# openLRS-APM.net
KiCad netlist of a schematic drawn in EAGLE
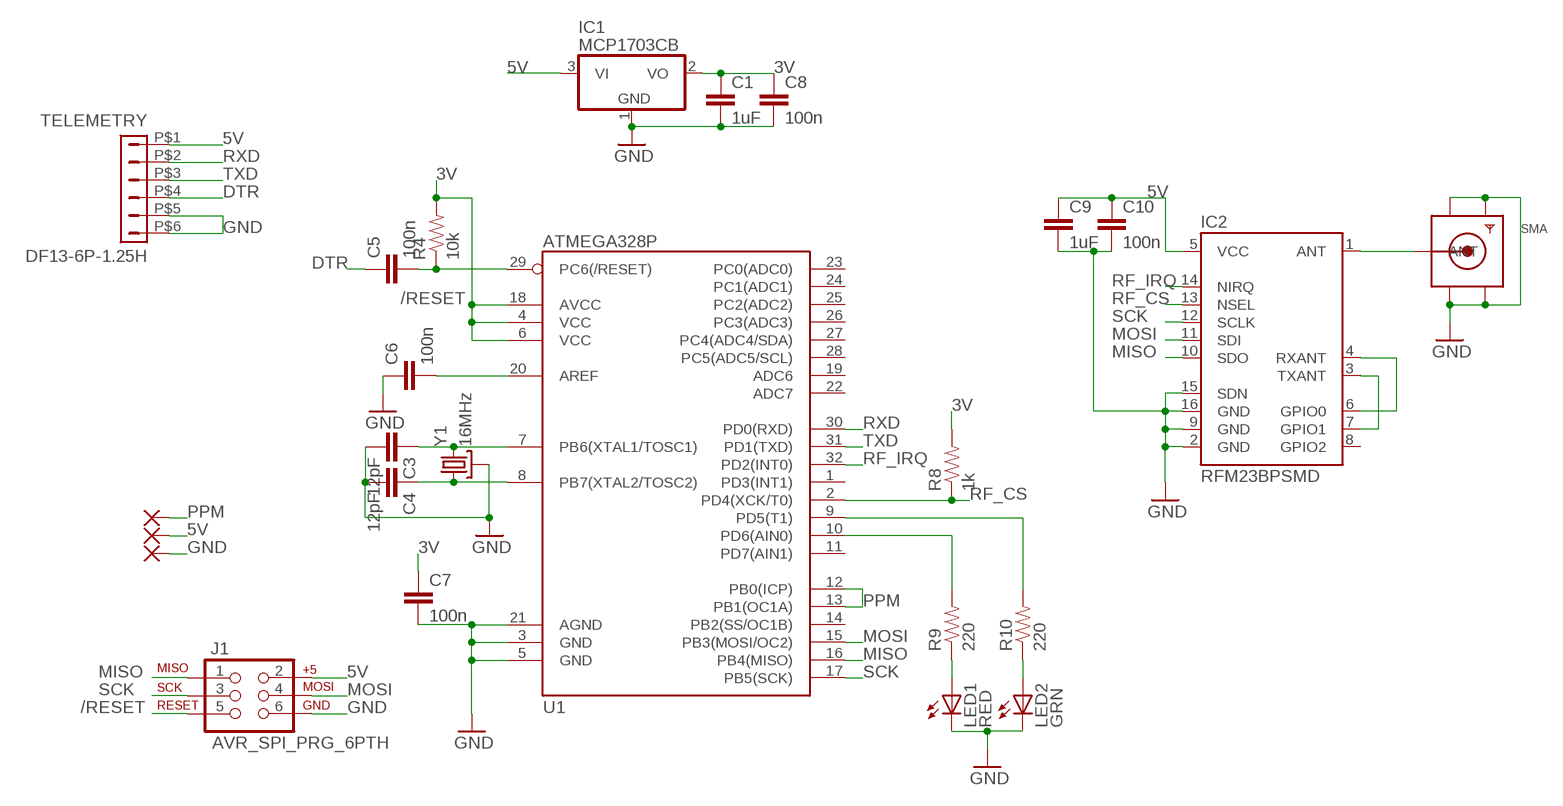
[diagram p0: schematic, sheet 1]

(export (version "E")
  (design (tool "Eeschema 10.0.6"))
  (components
    (comp (ref "C1")
      (value "1uF")
      (footprint "eagle-import:0805")
      (libsource (lib "eagle-import") (part "CAP0805"))
    )
    (comp (ref "C3")
      (value "12pF")
      (footprint "eagle-import:0805")
      (libsource (lib "eagle-import") (part "CAP0805"))
    )
    (comp (ref "C4")
      (value "12pF")
      (footprint "eagle-import:0805")
      (libsource (lib "eagle-import") (part "CAP0805"))
    )
    (comp (ref "C5")
      (value "100n")
      (footprint "eagle-import:0805")
      (libsource (lib "eagle-import") (part "CAP0805"))
    )
    (comp (ref "C6")
      (value "100n")
      (footprint "eagle-import:0805")
      (libsource (lib "eagle-import") (part "CAP0805"))
    )
    (comp (ref "C7")
      (value "100n")
      (footprint "eagle-import:0805")
      (libsource (lib "eagle-import") (part "CAP0805"))
    )
    (comp (ref "C8")
      (value "100n")
      (footprint "eagle-import:0805")
      (libsource (lib "eagle-import") (part "CAP0805"))
    )
    (comp (ref "C9")
      (value "1uF")
      (footprint "eagle-import:0805")
      (libsource (lib "eagle-import") (part "CAP0805"))
    )
    (comp (ref "C10")
      (value "100n")
      (footprint "eagle-import:0805")
      (libsource (lib "eagle-import") (part "CAP0805"))
    )
    (comp (ref "GND")
      (value "WIREPADSMD1,27-254")
      (footprint "eagle-import:SMD1,27-2,54")
      (libsource (lib "eagle-import") (part "WIREPADSMD1,27-254"))
    )
    (comp (ref "IC1")
      (value "MCP1703CB")
      (footprint "eagle-import:SOT23")
      (libsource (lib "eagle-import") (part "MCP1703CB"))
    )
    (comp (ref "IC2")
      (value "RFM23BPSMD")
      (footprint "eagle-import:RFM23BP-S2")
      (libsource (lib "eagle-import") (part "RFM23BPSMD"))
    )
    (comp (ref "J1")
      (value "AVR_SPI_PRG_6PTH")
      (footprint "eagle-import:2X3")
      (libsource (lib "eagle-import") (part "AVR_SPI_PRG_6PTH"))
    )
    (comp (ref "LED1")
      (value "RED")
      (footprint "eagle-import:SML0805")
      (libsource (lib "eagle-import") (part "LEDSML0805"))
    )
    (comp (ref "LED2")
      (value "GRN")
      (footprint "eagle-import:SML0805")
      (libsource (lib "eagle-import") (part "LEDSML0805"))
    )
    (comp (ref "PPM")
      (value "WIREPADSMD1,27-254")
      (footprint "eagle-import:SMD1,27-2,54")
      (libsource (lib "eagle-import") (part "WIREPADSMD1,27-254"))
    )
    (comp (ref "R4")
      (value "10k")
      (footprint "eagle-import:0805")
      (libsource (lib "eagle-import") (part "RESISTOR0805-RES"))
    )
    (comp (ref "R8")
      (value "1k")
      (footprint "eagle-import:0805")
      (libsource (lib "eagle-import") (part "RESISTOR0805-RES"))
    )
    (comp (ref "R9")
      (value "220")
      (footprint "eagle-import:0805")
      (libsource (lib "eagle-import") (part "RESISTOR0805-RES"))
    )
    (comp (ref "R10")
      (value "220")
      (footprint "eagle-import:0805")
      (libsource (lib "eagle-import") (part "RESISTOR0805-RES"))
    )
    (comp (ref "SMA")
      (value "SMACONNECTOR_EDGE")
      (footprint "eagle-import:SMA_EDGELAUNCH")
      (libsource (lib "eagle-import") (part "SMACONNECTOR_EDGE"))
    )
    (comp (ref "TELEMETRY")
      (value "DF13-6P-1.25H")
      (footprint "eagle-import:DF13A-6P-1.25H")
      (libsource (lib "eagle-import") (part "DF13-6P-1.25H"))
    )
    (comp (ref "U1")
      (value "ATMEGA328P")
      (footprint "eagle-import:TQFP32-08")
      (libsource (lib "eagle-import") (part "ATMEGA328_SMT"))
    )
    (comp (ref "VCC")
      (value "WIREPADSMD1,27-254")
      (footprint "eagle-import:SMD1,27-2,54")
      (libsource (lib "eagle-import") (part "WIREPADSMD1,27-254"))
    )
    (comp (ref "Y1")
      (value "16MHz")
      (footprint "eagle-import:CRYSTAL-SMD-5X3")
      (libsource (lib "eagle-import") (part "CRYSTAL3.2X2.5"))
    )
  )
  (nets
    (net (code "1") (name "/3V") (class "Default")
      (node (ref "C1") (pin "1") (pinfunction "1_1") (pintype "passive"))
      (node (ref "C7") (pin "1") (pinfunction "1_1") (pintype "passive"))
      (node (ref "C8") (pin "1") (pinfunction "1_1") (pintype "passive"))
      (node (ref "IC1") (pin "2") (pinfunction "VO_2") (pintype "passive"))
      (node (ref "R4") (pin "2") (pinfunction "2_2") (pintype "passive"))
      (node (ref "R8") (pin "2") (pinfunction "2_2") (pintype "passive"))
      (node (ref "U1") (pin "18") (pinfunction "AVCC_18") (pintype "bidirectional"))
      (node (ref "U1") (pin "4") (pinfunction "VCC_4") (pintype "bidirectional"))
      (node (ref "U1") (pin "6") (pinfunction "VCC_6") (pintype "bidirectional"))
    )
    (net (code "2") (name "/5V") (class "Default")
      (node (ref "C10") (pin "1") (pinfunction "1_1") (pintype "passive"))
      (node (ref "C9") (pin "1") (pinfunction "1_1") (pintype "passive"))
      (node (ref "IC1") (pin "3") (pinfunction "VI_3") (pintype "input"))
      (node (ref "IC2") (pin "5") (pinfunction "VCC_5") (pintype "bidirectional"))
      (node (ref "J1") (pin "2") (pinfunction "2_2") (pintype "passive"))
      (node (ref "TELEMETRY") (pin "P$1") (pinfunction "1_P$1") (pintype "passive"))
      (node (ref "VCC") (pin "1") (pinfunction "P_1") (pintype "passive"))
    )
    (net (code "3") (name "/DTR") (class "Default")
      (node (ref "C5") (pin "1") (pinfunction "1_1") (pintype "passive"))
      (node (ref "TELEMETRY") (pin "P$4") (pinfunction "4_P$4") (pintype "passive"))
    )
    (net (code "4") (name "/MISO") (class "Default")
      (node (ref "IC2") (pin "10") (pinfunction "SDO_10") (pintype "output"))
      (node (ref "J1") (pin "1") (pinfunction "1_1") (pintype "passive"))
      (node (ref "U1") (pin "16") (pinfunction "PB4(MISO)_16") (pintype "bidirectional"))
    )
    (net (code "5") (name "/MOSI") (class "Default")
      (node (ref "IC2") (pin "11") (pinfunction "SDI_11") (pintype "input"))
      (node (ref "J1") (pin "4") (pinfunction "4_4") (pintype "passive"))
      (node (ref "U1") (pin "15") (pinfunction "PB3(MOSI/OC2)_15") (pintype "bidirectional"))
    )
    (net (code "6") (name "/PPM") (class "Default")
      (node (ref "PPM") (pin "1") (pinfunction "P_1") (pintype "passive"))
      (node (ref "U1") (pin "12") (pinfunction "PB0(ICP)_12") (pintype "bidirectional"))
      (node (ref "U1") (pin "13") (pinfunction "PB1(OC1A)_13") (pintype "bidirectional"))
    )
    (net (code "7") (name "/RF_CS") (class "Default")
      (node (ref "IC2") (pin "13") (pinfunction "NSEL_13") (pintype "input"))
      (node (ref "R8") (pin "1") (pinfunction "1_1") (pintype "passive"))
      (node (ref "U1") (pin "2") (pinfunction "PD4(XCK/T0)_2") (pintype "bidirectional"))
    )
    (net (code "8") (name "/RF_IRQ") (class "Default")
      (node (ref "IC2") (pin "14") (pinfunction "NIRQ_14") (pintype "output"))
      (node (ref "U1") (pin "32") (pinfunction "PD2(INT0)_32") (pintype "bidirectional"))
    )
    (net (code "9") (name "/RXD") (class "Default")
      (node (ref "TELEMETRY") (pin "P$2") (pinfunction "2_P$2") (pintype "passive"))
      (node (ref "U1") (pin "30") (pinfunction "PD0(RXD)_30") (pintype "bidirectional"))
    )
    (net (code "10") (name "/SCK") (class "Default")
      (node (ref "IC2") (pin "12") (pinfunction "SCLK_12") (pintype "input"))
      (node (ref "J1") (pin "3") (pinfunction "3_3") (pintype "passive"))
      (node (ref "U1") (pin "17") (pinfunction "PB5(SCK)_17") (pintype "bidirectional"))
    )
    (net (code "11") (name "/TXD") (class "Default")
      (node (ref "TELEMETRY") (pin "P$3") (pinfunction "3_P$3") (pintype "passive"))
      (node (ref "U1") (pin "31") (pinfunction "PD1(TXD)_31") (pintype "bidirectional"))
    )
    (net (code "12") (name "/{slash}RESET") (class "Default")
      (node (ref "C5") (pin "2") (pinfunction "2_2") (pintype "passive"))
      (node (ref "J1") (pin "5") (pinfunction "5_5") (pintype "passive"))
      (node (ref "R4") (pin "1") (pinfunction "1_1") (pintype "passive"))
      (node (ref "U1") (pin "29") (pinfunction "PC6(/RESET)_29") (pintype "bidirectional"))
    )
    (net (code "13") (name "GND") (class "Default")
      (node (ref "C1") (pin "2") (pinfunction "2_2") (pintype "passive"))
      (node (ref "C10") (pin "2") (pinfunction "2_2") (pintype "passive"))
      (node (ref "C3") (pin "2") (pinfunction "2_2") (pintype "passive"))
      (node (ref "C4") (pin "2") (pinfunction "2_2") (pintype "passive"))
      (node (ref "C6") (pin "1") (pinfunction "1_1") (pintype "passive"))
      (node (ref "C7") (pin "2") (pinfunction "2_2") (pintype "passive"))
      (node (ref "C8") (pin "2") (pinfunction "2_2") (pintype "passive"))
      (node (ref "C9") (pin "2") (pinfunction "2_2") (pintype "passive"))
      (node (ref "GND") (pin "1") (pinfunction "P_1") (pintype "passive"))
      (node (ref "IC1") (pin "1") (pinfunction "GND_1") (pintype "passive"))
      (node (ref "IC2") (pin "15") (pinfunction "SDN_15") (pintype "input"))
      (node (ref "IC2") (pin "16") (pinfunction "GND_16") (pintype "power_in"))
      (node (ref "IC2") (pin "2") (pinfunction "GND_2") (pintype "power_in"))
      (node (ref "IC2") (pin "9") (pinfunction "GND_9") (pintype "power_in"))
      (node (ref "J1") (pin "6") (pinfunction "6_6") (pintype "passive"))
      (node (ref "LED1") (pin "C") (pinfunction "C_C") (pintype "passive"))
      (node (ref "LED2") (pin "C") (pinfunction "C_C") (pintype "passive"))
      (node (ref "SMA") (pin "GND@1") (pinfunction "GND4_GND@1") (pintype "power_in"))
      (node (ref "SMA") (pin "GND@2") (pinfunction "GND3_GND@2") (pintype "power_in"))
      (node (ref "SMA") (pin "GND@3") (pinfunction "GND2_GND@3") (pintype "power_in"))
      (node (ref "SMA") (pin "GND@4") (pinfunction "GND1_GND@4") (pintype "power_in"))
      (node (ref "TELEMETRY") (pin "P$5") (pinfunction "5_P$5") (pintype "passive"))
      (node (ref "TELEMETRY") (pin "P$6") (pinfunction "6_P$6") (pintype "passive"))
      (node (ref "U1") (pin "21") (pinfunction "AGND_21") (pintype "bidirectional"))
      (node (ref "U1") (pin "3") (pinfunction "GND_3") (pintype "bidirectional"))
      (node (ref "U1") (pin "5") (pinfunction "GND_5") (pintype "bidirectional"))
      (node (ref "Y1") (pin "2") (pinfunction "GND_2") (pintype "power_in"))
      (node (ref "Y1") (pin "4") (pinfunction "GND_4") (pintype "power_in"))
    )
    (net (code "14") (name "Net-(IC2-ANT)") (class "Default")
      (node (ref "IC2") (pin "1") (pinfunction "ANT_1") (pintype "bidirectional"))
      (node (ref "SMA") (pin "P") (pinfunction "ANT_P") (pintype "bidirectional"))
    )
    (net (code "15") (name "Net-(IC2-GPIO0)") (class "Default")
      (node (ref "IC2") (pin "4") (pinfunction "RXANT_4") (pintype "input"))
      (node (ref "IC2") (pin "6") (pinfunction "GPIO0_6") (pintype "bidirectional"))
    )
    (net (code "16") (name "Net-(IC2-GPIO1)") (class "Default")
      (node (ref "IC2") (pin "3") (pinfunction "TXANT_3") (pintype "input"))
      (node (ref "IC2") (pin "7") (pinfunction "GPIO1_7") (pintype "bidirectional"))
    )
    (net (code "17") (name "Net-(LED1-PadA)") (class "Default")
      (node (ref "LED1") (pin "A") (pinfunction "A_A") (pintype "passive"))
      (node (ref "R9") (pin "1") (pinfunction "1_1") (pintype "passive"))
    )
    (net (code "18") (name "Net-(LED2-PadA)") (class "Default")
      (node (ref "LED2") (pin "A") (pinfunction "A_A") (pintype "passive"))
      (node (ref "R10") (pin "1") (pinfunction "1_1") (pintype "passive"))
    )
    (net (code "19") (name "Net-(U1-AREF)") (class "Default")
      (node (ref "C6") (pin "2") (pinfunction "2_2") (pintype "passive"))
      (node (ref "U1") (pin "20") (pinfunction "AREF_20") (pintype "bidirectional"))
    )
    (net (code "20") (name "Net-(U1-PB6(XTAL1{slash}TOSC1))") (class "Default")
      (node (ref "C3") (pin "1") (pinfunction "1_1") (pintype "passive"))
      (node (ref "U1") (pin "7") (pinfunction "PB6(XTAL1/TOSC1)_7") (pintype "bidirectional"))
      (node (ref "Y1") (pin "3") (pinfunction "2_3") (pintype "passive"))
    )
    (net (code "21") (name "Net-(U1-PB7(XTAL2{slash}TOSC2))") (class "Default")
      (node (ref "C4") (pin "1") (pinfunction "1_1") (pintype "passive"))
      (node (ref "U1") (pin "8") (pinfunction "PB7(XTAL2/TOSC2)_8") (pintype "bidirectional"))
      (node (ref "Y1") (pin "1") (pinfunction "1_1") (pintype "passive"))
    )
    (net (code "22") (name "Net-(U1-PD5(T1))") (class "Default")
      (node (ref "R10") (pin "2") (pinfunction "2_2") (pintype "passive"))
      (node (ref "U1") (pin "9") (pinfunction "PD5(T1)_9") (pintype "bidirectional"))
    )
    (net (code "23") (name "Net-(U1-PD6(AIN0))") (class "Default")
      (node (ref "R9") (pin "2") (pinfunction "2_2") (pintype "passive"))
      (node (ref "U1") (pin "10") (pinfunction "PD6(AIN0)_10") (pintype "bidirectional"))
    )
    (net (code "24") (name "unconnected-(IC2-GPIO2-Pad8)") (class "Default")
      (node (ref "IC2") (pin "8") (pinfunction "GPIO2_8") (pintype "bidirectional"))
    )
    (net (code "25") (name "unconnected-(U1-ADC6-Pad19)") (class "Default")
      (node (ref "U1") (pin "19") (pinfunction "ADC6_19") (pintype "bidirectional"))
    )
    (net (code "26") (name "unconnected-(U1-ADC7-Pad22)") (class "Default")
      (node (ref "U1") (pin "22") (pinfunction "ADC7_22") (pintype "bidirectional"))
    )
    (net (code "27") (name "unconnected-(U1-PB2(SS{slash}OC1B)-Pad14)") (class "Default")
      (node (ref "U1") (pin "14") (pinfunction "PB2(SS/OC1B)_14") (pintype "bidirectional"))
    )
    (net (code "28") (name "unconnected-(U1-PC0(ADC0)-Pad23)") (class "Default")
      (node (ref "U1") (pin "23") (pinfunction "PC0(ADC0)_23") (pintype "bidirectional"))
    )
    (net (code "29") (name "unconnected-(U1-PC1(ADC1)-Pad24)") (class "Default")
      (node (ref "U1") (pin "24") (pinfunction "PC1(ADC1)_24") (pintype "bidirectional"))
    )
    (net (code "30") (name "unconnected-(U1-PC2(ADC2)-Pad25)") (class "Default")
      (node (ref "U1") (pin "25") (pinfunction "PC2(ADC2)_25") (pintype "bidirectional"))
    )
    (net (code "31") (name "unconnected-(U1-PC3(ADC3)-Pad26)") (class "Default")
      (node (ref "U1") (pin "26") (pinfunction "PC3(ADC3)_26") (pintype "bidirectional"))
    )
    (net (code "32") (name "unconnected-(U1-PC4(ADC4{slash}SDA)-Pad27)") (class "Default")
      (node (ref "U1") (pin "27") (pinfunction "PC4(ADC4/SDA)_27") (pintype "bidirectional"))
    )
    (net (code "33") (name "unconnected-(U1-PC5(ADC5{slash}SCL)-Pad28)") (class "Default")
      (node (ref "U1") (pin "28") (pinfunction "PC5(ADC5/SCL)_28") (pintype "bidirectional"))
    )
    (net (code "34") (name "unconnected-(U1-PD3(INT1)-Pad1)") (class "Default")
      (node (ref "U1") (pin "1") (pinfunction "PD3(INT1)_1") (pintype "bidirectional"))
    )
    (net (code "35") (name "unconnected-(U1-PD7(AIN1)-Pad11)") (class "Default")
      (node (ref "U1") (pin "11") (pinfunction "PD7(AIN1)_11") (pintype "bidirectional"))
    )
  )
)
